# Tugas_rangkaian_op_amp.net
KiCad netlist of a schematic drawn in EAGLE
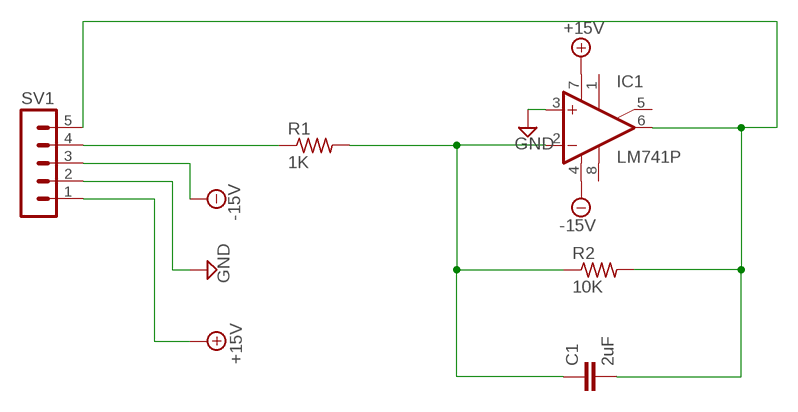
[diagram p0: schematic, sheet 1]

(export (version "E")
  (design (tool "Eeschema 10.0.6"))
  (components
    (comp (ref "C1")
      (value "2uF")
      (footprint "eagle-import:C025-024X044")
      (libsource (lib "eagle-import") (part "C-EU025-024X044"))
    )
    (comp (ref "IC1")
      (value "LM741P")
      (footprint "eagle-import:DIL08")
      (libsource (lib "eagle-import") (part "741PLM"))
    )
    (comp (ref "R1")
      (value "1K")
      (footprint "eagle-import:0204_5")
      (libsource (lib "eagle-import") (part "R-US_0204/5"))
    )
    (comp (ref "R2")
      (value "10K")
      (footprint "eagle-import:0204_5")
      (libsource (lib "eagle-import") (part "R-US_0204/5"))
    )
    (comp (ref "SV1")
      (value "MA05-1")
      (footprint "eagle-import:MA05-1")
      (libsource (lib "eagle-import") (part "MA05-1"))
    )
  )
  (nets
    (net (code "1") (name "+15V") (class "Default")
      (node (ref "IC1") (pin "7") (pinfunction "V+_7") (pintype "power_in"))
      (node (ref "SV1") (pin "1") (pinfunction "1_1") (pintype "passive"))
    )
    (net (code "2") (name "-15V") (class "Default")
      (node (ref "IC1") (pin "4") (pinfunction "V-_4") (pintype "power_in"))
      (node (ref "SV1") (pin "3") (pinfunction "3_3") (pintype "passive"))
    )
    (net (code "3") (name "GND") (class "Default")
      (node (ref "IC1") (pin "3") (pinfunction "+IN_3") (pintype "input"))
      (node (ref "SV1") (pin "2") (pinfunction "2_2") (pintype "passive"))
    )
    (net (code "4") (name "Net-(IC1--IN)") (class "Default")
      (node (ref "C1") (pin "1") (pinfunction "1_1") (pintype "passive"))
      (node (ref "IC1") (pin "2") (pinfunction "-IN_2") (pintype "input"))
      (node (ref "R1") (pin "2") (pinfunction "2_2") (pintype "passive"))
      (node (ref "R2") (pin "1") (pinfunction "1_1") (pintype "passive"))
    )
    (net (code "5") (name "Net-(IC1-OUT)") (class "Default")
      (node (ref "C1") (pin "2") (pinfunction "2_2") (pintype "passive"))
      (node (ref "IC1") (pin "6") (pinfunction "OUT_6") (pintype "output"))
      (node (ref "R2") (pin "2") (pinfunction "2_2") (pintype "passive"))
      (node (ref "SV1") (pin "5") (pinfunction "5_5") (pintype "passive"))
    )
    (net (code "6") (name "Net-(R1-Pad1)") (class "Default")
      (node (ref "R1") (pin "1") (pinfunction "1_1") (pintype "passive"))
      (node (ref "SV1") (pin "4") (pinfunction "4_4") (pintype "passive"))
    )
    (net (code "7") (name "unconnected-(IC1-ON1-Pad1)") (class "Default")
      (node (ref "IC1") (pin "1") (pinfunction "ON1_1") (pintype "passive"))
    )
    (net (code "8") (name "unconnected-(IC1-ON2-Pad5)") (class "Default")
      (node (ref "IC1") (pin "5") (pinfunction "ON2_5") (pintype "passive"))
    )
    (net (code "9") (name "unconnected-(IC1-OPT-Pad8)") (class "Default")
      (node (ref "IC1") (pin "8") (pinfunction "OPT_8") (pintype "passive"))
    )
  )
)
